# VI_595X5_V1_1.net
KiCad netlist of a schematic drawn in Altium Designer
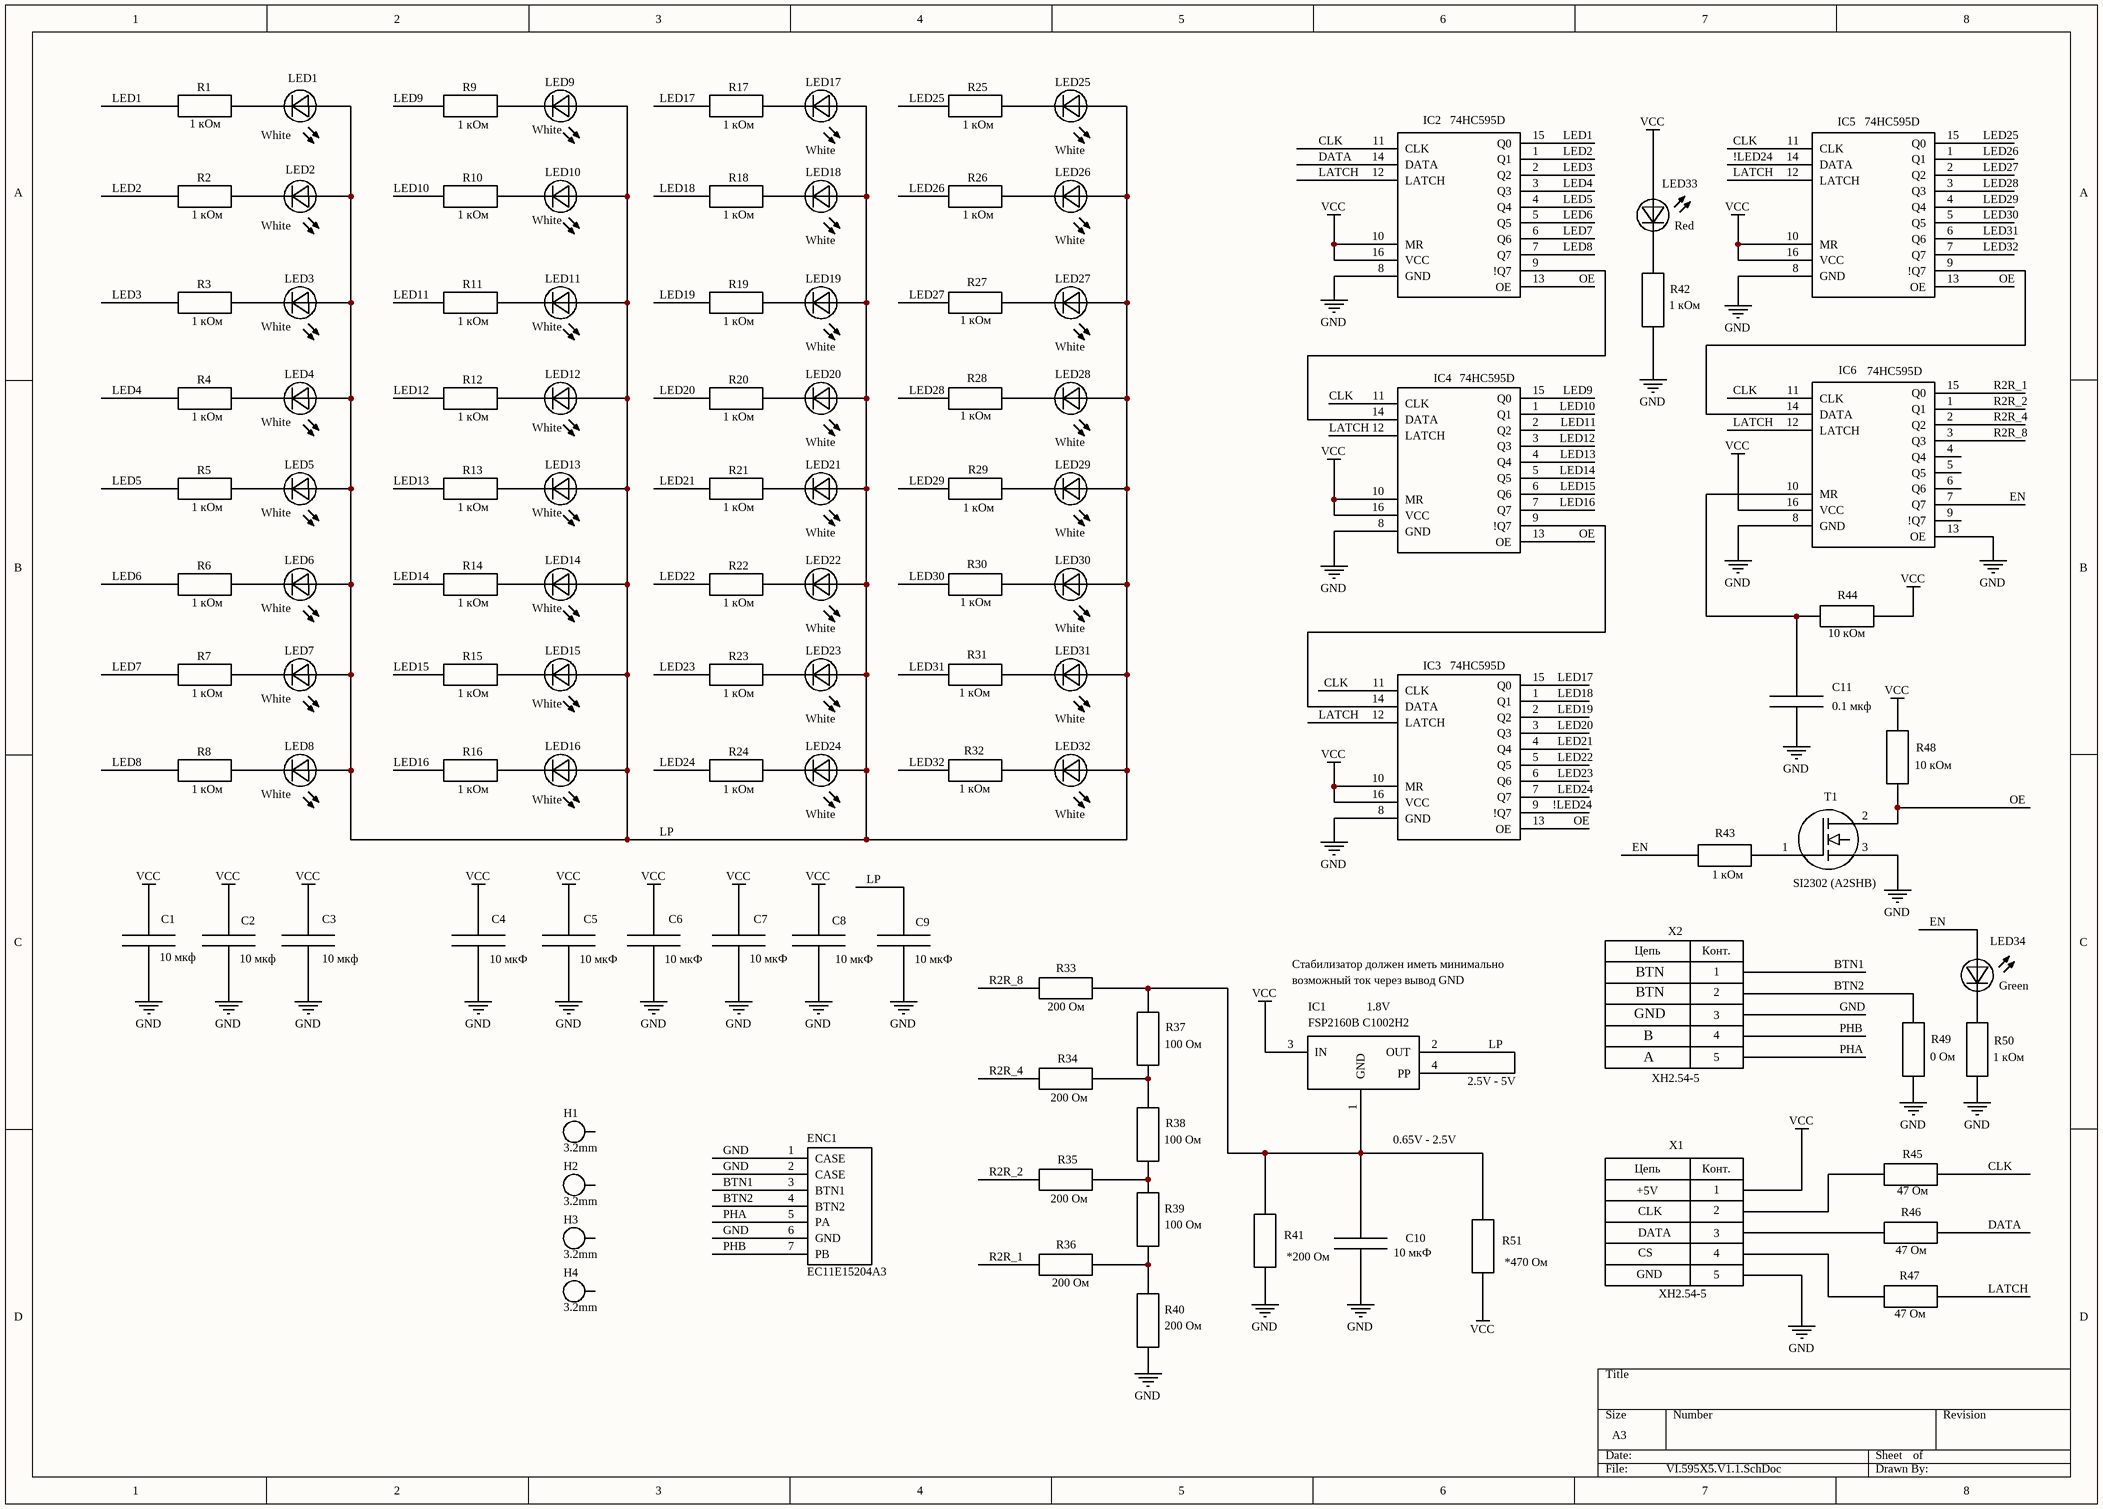
[diagram p0: VI.595X5.V1.1.SchDoc]

(export (version "E")
  (design (tool "Eeschema 10.0.6"))
  (components
    (comp (ref "C1")
      (value "10 мкф")
      (footprint "Конденсатор SMD Case 1206")
      (libsource (lib "S83") (part "Конденсатор"))
    )
    (comp (ref "C2")
      (value "10 мкф")
      (footprint "Конденсатор SMD Case 1206")
      (libsource (lib "S83") (part "Конденсатор"))
    )
    (comp (ref "C3")
      (value "10 мкф")
      (footprint "Конденсатор SMD Case 1206")
      (libsource (lib "S83") (part "Конденсатор"))
    )
    (comp (ref "C4")
      (value "10 мкФ")
      (footprint "Конденсатор SMD Case 1206")
      (libsource (lib "S83") (part "Конденсатор"))
    )
    (comp (ref "C5")
      (value "10 мкФ")
      (footprint "Конденсатор SMD Case 1206")
      (libsource (lib "S83") (part "Конденсатор"))
    )
    (comp (ref "C6")
      (value "10 мкФ")
      (footprint "Конденсатор SMD Case 1206")
      (libsource (lib "S83") (part "Конденсатор"))
    )
    (comp (ref "C7")
      (value "10 мкФ")
      (footprint "Конденсатор SMD Case 1206")
      (libsource (lib "S83") (part "Конденсатор"))
    )
    (comp (ref "C8")
      (value "10 мкФ")
      (footprint "Конденсатор SMD Case 1206")
      (libsource (lib "S83") (part "Конденсатор"))
    )
    (comp (ref "C9")
      (value "10 мкФ")
      (footprint "Конденсатор SMD Case 1206")
      (libsource (lib "S83") (part "Конденсатор"))
    )
    (comp (ref "C10")
      (value "10 мкФ")
      (footprint "Конденсатор SMD Case 1206")
      (libsource (lib "S83") (part "Конденсатор"))
    )
    (comp (ref "C11")
      (value "0.1 мкф")
      (footprint "Конденсатор SMD Case 1206")
      (libsource (lib "S83") (part "Конденсатор"))
    )
    (comp (ref "ENC1")
      (value "EC11E15204A3")
      (footprint "Encoder")
      (libsource (lib "S83") (part "Encoder_01"))
    )
    (comp (ref "H1")
      (value "3.2mm")
      (footprint "Отверстие 3,2")
      (libsource (lib "S83") (part "Отверстие монтажное"))
    )
    (comp (ref "H2")
      (value "3.2mm")
      (footprint "Отверстие 3,2")
      (libsource (lib "S83") (part "Отверстие монтажное"))
    )
    (comp (ref "H3")
      (value "3.2mm")
      (footprint "Отверстие 3,2")
      (libsource (lib "S83") (part "Отверстие монтажное"))
    )
    (comp (ref "H4")
      (value "3.2mm")
      (footprint "Отверстие 3,2")
      (libsource (lib "S83") (part "Отверстие монтажное"))
    )
    (comp (ref "IC1")
      (value "FSP2160B C1002H2")
      (footprint "SOT-223")
      (libsource (lib "S83_IC") (part "FSP2160B J1003H1"))
    )
    (comp (ref "IC2") (value "74HC595D") (footprint "SO-16") (libsource (lib "S83_IC") (part "74HC595D")))
    (comp (ref "IC3") (value "74HC595D") (footprint "SO-16") (libsource (lib "S83_IC") (part "74HC595D")))
    (comp (ref "IC4") (value "74HC595D") (footprint "SO-16") (libsource (lib "S83_IC") (part "74HC595D")))
    (comp (ref "IC5") (value "74HC595D") (footprint "SO-16") (libsource (lib "S83_IC") (part "74HC595D")))
    (comp (ref "IC6") (value "74HC595D") (footprint "SO-16") (libsource (lib "S83_IC") (part "74HC595D")))
    (comp (ref "LED1")
      (value "White")
      (footprint "Светодиод  5x2 mm")
      (libsource (lib "S83") (part "Светодиод"))
    )
    (comp (ref "LED2")
      (value "White")
      (footprint "Светодиод  5x2 mm")
      (libsource (lib "S83") (part "Светодиод"))
    )
    (comp (ref "LED3")
      (value "White")
      (footprint "Светодиод  5x2 mm")
      (libsource (lib "S83") (part "Светодиод"))
    )
    (comp (ref "LED4")
      (value "White")
      (footprint "Светодиод  5x2 mm")
      (libsource (lib "S83") (part "Светодиод"))
    )
    (comp (ref "LED5")
      (value "White")
      (footprint "Светодиод  5x2 mm")
      (libsource (lib "S83") (part "Светодиод"))
    )
    (comp (ref "LED6")
      (value "White")
      (footprint "Светодиод  5x2 mm")
      (libsource (lib "S83") (part "Светодиод"))
    )
    (comp (ref "LED7")
      (value "White")
      (footprint "Светодиод  5x2 mm")
      (libsource (lib "S83") (part "Светодиод"))
    )
    (comp (ref "LED8")
      (value "White")
      (footprint "Светодиод  5x2 mm")
      (libsource (lib "S83") (part "Светодиод"))
    )
    (comp (ref "LED9")
      (value "White")
      (footprint "Светодиод  5x2 mm")
      (libsource (lib "S83") (part "Светодиод"))
    )
    (comp (ref "LED10")
      (value "White")
      (footprint "Светодиод  5x2 mm")
      (libsource (lib "S83") (part "Светодиод"))
    )
    (comp (ref "LED11")
      (value "White")
      (footprint "Светодиод  5x2 mm")
      (libsource (lib "S83") (part "Светодиод"))
    )
    (comp (ref "LED12")
      (value "White")
      (footprint "Светодиод  5x2 mm")
      (libsource (lib "S83") (part "Светодиод"))
    )
    (comp (ref "LED13")
      (value "White")
      (footprint "Светодиод  5x2 mm")
      (libsource (lib "S83") (part "Светодиод"))
    )
    (comp (ref "LED14")
      (value "White")
      (footprint "Светодиод  5x2 mm")
      (libsource (lib "S83") (part "Светодиод"))
    )
    (comp (ref "LED15")
      (value "White")
      (footprint "Светодиод  5x2 mm")
      (libsource (lib "S83") (part "Светодиод"))
    )
    (comp (ref "LED16")
      (value "White")
      (footprint "Светодиод  5x2 mm")
      (libsource (lib "S83") (part "Светодиод"))
    )
    (comp (ref "LED17")
      (value "White")
      (footprint "Светодиод  5x2 mm")
      (libsource (lib "S83") (part "Светодиод"))
    )
    (comp (ref "LED18")
      (value "White")
      (footprint "Светодиод  5x2 mm")
      (libsource (lib "S83") (part "Светодиод"))
    )
    (comp (ref "LED19")
      (value "White")
      (footprint "Светодиод  5x2 mm")
      (libsource (lib "S83") (part "Светодиод"))
    )
    (comp (ref "LED20")
      (value "White")
      (footprint "Светодиод  5x2 mm")
      (libsource (lib "S83") (part "Светодиод"))
    )
    (comp (ref "LED21")
      (value "White")
      (footprint "Светодиод  5x2 mm")
      (libsource (lib "S83") (part "Светодиод"))
    )
    (comp (ref "LED22")
      (value "White")
      (footprint "Светодиод  5x2 mm")
      (libsource (lib "S83") (part "Светодиод"))
    )
    (comp (ref "LED23")
      (value "White")
      (footprint "Светодиод  5x2 mm")
      (libsource (lib "S83") (part "Светодиод"))
    )
    (comp (ref "LED24")
      (value "White")
      (footprint "Светодиод  5x2 mm")
      (libsource (lib "S83") (part "Светодиод"))
    )
    (comp (ref "LED25")
      (value "White")
      (footprint "Светодиод  5x2 mm")
      (libsource (lib "S83") (part "Светодиод"))
    )
    (comp (ref "LED26")
      (value "White")
      (footprint "Светодиод  5x2 mm")
      (libsource (lib "S83") (part "Светодиод"))
    )
    (comp (ref "LED27")
      (value "White")
      (footprint "Светодиод  5x2 mm")
      (libsource (lib "S83") (part "Светодиод"))
    )
    (comp (ref "LED28")
      (value "White")
      (footprint "Светодиод  5x2 mm")
      (libsource (lib "S83") (part "Светодиод"))
    )
    (comp (ref "LED29")
      (value "White")
      (footprint "Светодиод  5x2 mm")
      (libsource (lib "S83") (part "Светодиод"))
    )
    (comp (ref "LED30")
      (value "White")
      (footprint "Светодиод  5x2 mm")
      (libsource (lib "S83") (part "Светодиод"))
    )
    (comp (ref "LED31")
      (value "White")
      (footprint "Светодиод  5x2 mm")
      (libsource (lib "S83") (part "Светодиод"))
    )
    (comp (ref "LED32")
      (value "White")
      (footprint "Светодиод  5x2 mm")
      (libsource (lib "S83") (part "Светодиод"))
    )
    (comp (ref "LED33")
      (value "Red")
      (footprint "SMD 1206 Светодиод ВАЙТ")
      (libsource (lib "S83") (part "Светодиод"))
    )
    (comp (ref "LED34")
      (value "Green")
      (footprint "SMD 1206 Светодиод ВАЙТ")
      (libsource (lib "S83") (part "Светодиод"))
    )
    (comp (ref "R1")
      (value "1 кОм")
      (footprint "SMD 0805 Резистор")
      (libsource (lib "S83") (part "Резистор"))
    )
    (comp (ref "R2")
      (value "1 кОм")
      (footprint "SMD 0805 Резистор")
      (libsource (lib "S83") (part "Резистор"))
    )
    (comp (ref "R3")
      (value "1 кОм")
      (footprint "SMD 0805 Резистор")
      (libsource (lib "S83") (part "Резистор"))
    )
    (comp (ref "R4")
      (value "1 кОм")
      (footprint "SMD 0805 Резистор")
      (libsource (lib "S83") (part "Резистор"))
    )
    (comp (ref "R5")
      (value "1 кОм")
      (footprint "SMD 0805 Резистор")
      (libsource (lib "S83") (part "Резистор"))
    )
    (comp (ref "R6")
      (value "1 кОм")
      (footprint "SMD 0805 Резистор")
      (libsource (lib "S83") (part "Резистор"))
    )
    (comp (ref "R7")
      (value "1 кОм")
      (footprint "SMD 0805 Резистор")
      (libsource (lib "S83") (part "Резистор"))
    )
    (comp (ref "R8")
      (value "1 кОм")
      (footprint "SMD 0805 Резистор")
      (libsource (lib "S83") (part "Резистор"))
    )
    (comp (ref "R9")
      (value "1 кОм")
      (footprint "SMD 0805 Резистор")
      (libsource (lib "S83") (part "Резистор"))
    )
    (comp (ref "R10")
      (value "1 кОм")
      (footprint "SMD 0805 Резистор")
      (libsource (lib "S83") (part "Резистор"))
    )
    (comp (ref "R11")
      (value "1 кОм")
      (footprint "SMD 0805 Резистор")
      (libsource (lib "S83") (part "Резистор"))
    )
    (comp (ref "R12")
      (value "1 кОм")
      (footprint "SMD 0805 Резистор")
      (libsource (lib "S83") (part "Резистор"))
    )
    (comp (ref "R13")
      (value "1 кОм")
      (footprint "SMD 0805 Резистор")
      (libsource (lib "S83") (part "Резистор"))
    )
    (comp (ref "R14")
      (value "1 кОм")
      (footprint "SMD 0805 Резистор")
      (libsource (lib "S83") (part "Резистор"))
    )
    (comp (ref "R15")
      (value "1 кОм")
      (footprint "SMD 0805 Резистор")
      (libsource (lib "S83") (part "Резистор"))
    )
    (comp (ref "R16")
      (value "1 кОм")
      (footprint "SMD 0805 Резистор")
      (libsource (lib "S83") (part "Резистор"))
    )
    (comp (ref "R17")
      (value "1 кОм")
      (footprint "SMD 0805 Резистор")
      (libsource (lib "S83") (part "Резистор"))
    )
    (comp (ref "R18")
      (value "1 кОм")
      (footprint "SMD 0805 Резистор")
      (libsource (lib "S83") (part "Резистор"))
    )
    (comp (ref "R19")
      (value "1 кОм")
      (footprint "SMD 0805 Резистор")
      (libsource (lib "S83") (part "Резистор"))
    )
    (comp (ref "R20")
      (value "1 кОм")
      (footprint "SMD 0805 Резистор")
      (libsource (lib "S83") (part "Резистор"))
    )
    (comp (ref "R21")
      (value "1 кОм")
      (footprint "SMD 0805 Резистор")
      (libsource (lib "S83") (part "Резистор"))
    )
    (comp (ref "R22")
      (value "1 кОм")
      (footprint "SMD 0805 Резистор")
      (libsource (lib "S83") (part "Резистор"))
    )
    (comp (ref "R23")
      (value "1 кОм")
      (footprint "SMD 0805 Резистор")
      (libsource (lib "S83") (part "Резистор"))
    )
    (comp (ref "R24")
      (value "1 кОм")
      (footprint "SMD 0805 Резистор")
      (libsource (lib "S83") (part "Резистор"))
    )
    (comp (ref "R25")
      (value "1 кОм")
      (footprint "SMD 0805 Резистор")
      (libsource (lib "S83") (part "Резистор"))
    )
    (comp (ref "R26")
      (value "1 кОм")
      (footprint "SMD 0805 Резистор")
      (libsource (lib "S83") (part "Резистор"))
    )
    (comp (ref "R27")
      (value "1 кОм")
      (footprint "SMD 0805 Резистор")
      (libsource (lib "S83") (part "Резистор"))
    )
    (comp (ref "R28")
      (value "1 кОм")
      (footprint "SMD 0805 Резистор")
      (libsource (lib "S83") (part "Резистор"))
    )
    (comp (ref "R29")
      (value "1 кОм")
      (footprint "SMD 0805 Резистор")
      (libsource (lib "S83") (part "Резистор"))
    )
    (comp (ref "R30")
      (value "1 кОм")
      (footprint "SMD 0805 Резистор")
      (libsource (lib "S83") (part "Резистор"))
    )
    (comp (ref "R31")
      (value "1 кОм")
      (footprint "SMD 0805 Резистор")
      (libsource (lib "S83") (part "Резистор"))
    )
    (comp (ref "R32")
      (value "1 кОм")
      (footprint "SMD 0805 Резистор")
      (libsource (lib "S83") (part "Резистор"))
    )
    (comp (ref "R33")
      (value "200 Ом")
      (footprint "SMD 0805 Резистор")
      (libsource (lib "S83") (part "Резистор"))
    )
    (comp (ref "R34")
      (value "200 Ом")
      (footprint "SMD 0805 Резистор")
      (libsource (lib "S83") (part "Резистор"))
    )
    (comp (ref "R35")
      (value "200 Ом")
      (footprint "SMD 0805 Резистор")
      (libsource (lib "S83") (part "Резистор"))
    )
    (comp (ref "R36")
      (value "200 Ом")
      (footprint "SMD 0805 Резистор")
      (libsource (lib "S83") (part "Резистор"))
    )
    (comp (ref "R37")
      (value "100 Ом")
      (footprint "SMD 0805 Резистор")
      (libsource (lib "S83") (part "Резистор"))
    )
    (comp (ref "R38")
      (value "100 Ом")
      (footprint "SMD 0805 Резистор")
      (libsource (lib "S83") (part "Резистор"))
    )
    (comp (ref "R39")
      (value "100 Ом")
      (footprint "SMD 0805 Резистор")
      (libsource (lib "S83") (part "Резистор"))
    )
    (comp (ref "R40")
      (value "200 Ом")
      (footprint "SMD 0805 Резистор")
      (libsource (lib "S83") (part "Резистор"))
    )
    (comp (ref "R41")
      (value "*200 Ом")
      (footprint "SMD 0805 Резистор")
      (libsource (lib "S83") (part "Резистор"))
    )
    (comp (ref "R42")
      (value "1 кОм")
      (footprint "SMD 0805 Резистор")
      (libsource (lib "S83") (part "Резистор"))
    )
    (comp (ref "R43")
      (value "1 кОм")
      (footprint "SMD 0805 Резистор")
      (libsource (lib "S83") (part "Резистор"))
    )
    (comp (ref "R44")
      (value "10 кОм")
      (footprint "SMD 0805 Резистор")
      (libsource (lib "S83") (part "Резистор"))
    )
    (comp (ref "R45")
      (value "47 Ом")
      (footprint "SMD 0805 Резистор")
      (libsource (lib "S83") (part "Резистор"))
    )
    (comp (ref "R46")
      (value "47 Ом")
      (footprint "SMD 0805 Резистор")
      (libsource (lib "S83") (part "Резистор"))
    )
    (comp (ref "R47")
      (value "47 Ом")
      (footprint "SMD 0805 Резистор")
      (libsource (lib "S83") (part "Резистор"))
    )
    (comp (ref "R48")
      (value "10 кОм")
      (footprint "SMD 0805 Резистор")
      (libsource (lib "S83") (part "Резистор"))
    )
    (comp (ref "R49")
      (value "0 Ом")
      (footprint "SMD 0805 Резистор")
      (libsource (lib "S83") (part "Резистор"))
    )
    (comp (ref "R50")
      (value "1 кОм")
      (footprint "SMD 0805 Резистор")
      (libsource (lib "S83") (part "Резистор"))
    )
    (comp (ref "R51")
      (value "*470 Ом")
      (footprint "SMD 0805 Резистор")
      (libsource (lib "S83") (part "Резистор"))
    )
    (comp (ref "T1")
      (value "SI2302 (A2SHB)")
      (footprint "SMD SOT-23 Транзистор 3 pin")
      (libsource (lib "S83") (part "Транзистор MOSFET N-конал (как n-p-n)"))
    )
    (comp (ref "X1")
      (value "XH2.54-5")
      (footprint "(1x5)pin XH 2.54 Header")
      (libsource (lib "S83_connectors") (part "(1x5) pin 2.54 Header"))
    )
    (comp (ref "X2")
      (value "XH2.54-5")
      (footprint "(1x5)pin XH 2.54 Header")
      (libsource (lib "S83_connectors") (part "(1x5) pin 2.54 Header"))
    )
  )
  (nets
    (net (code "1") (name "/!LED24") (class "Default")
      (node (ref "IC3") (pin "9") (pinfunction "!Q7_9") (pintype "passive"))
      (node (ref "IC5") (pin "14") (pinfunction "DATA_14") (pintype "passive"))
    )
    (net (code "2") (name "/BTN1") (class "Default")
      (node (ref "ENC1") (pin "3") (pinfunction "BTN1_3") (pintype "passive"))
      (node (ref "X2") (pin "1") (pinfunction "1_1") (pintype "passive"))
    )
    (net (code "3") (name "/BTN2") (class "Default")
      (node (ref "ENC1") (pin "4") (pinfunction "BTN2_4") (pintype "passive"))
      (node (ref "R49") (pin "2") (pinfunction "right_2") (pintype "passive"))
      (node (ref "X2") (pin "2") (pinfunction "2_2") (pintype "passive"))
    )
    (net (code "4") (name "/CLK") (class "Default")
      (node (ref "IC2") (pin "11") (pinfunction "CLK_11") (pintype "passive"))
      (node (ref "IC3") (pin "11") (pinfunction "CLK_11") (pintype "passive"))
      (node (ref "IC4") (pin "11") (pinfunction "CLK_11") (pintype "passive"))
      (node (ref "IC5") (pin "11") (pinfunction "CLK_11") (pintype "passive"))
      (node (ref "IC6") (pin "11") (pinfunction "CLK_11") (pintype "passive"))
      (node (ref "R45") (pin "1") (pinfunction "left_1") (pintype "passive"))
    )
    (net (code "5") (name "/DATA") (class "Default")
      (node (ref "IC2") (pin "14") (pinfunction "DATA_14") (pintype "passive"))
      (node (ref "R46") (pin "1") (pinfunction "left_1") (pintype "passive"))
    )
    (net (code "6") (name "/EN") (class "Default")
      (node (ref "IC6") (pin "7") (pinfunction "Q7_7") (pintype "passive"))
      (node (ref "LED34") (pin "1") (pinfunction "А_1") (pintype "passive"))
      (node (ref "R43") (pin "2") (pinfunction "right_2") (pintype "passive"))
    )
    (net (code "7") (name "/LATCH") (class "Default")
      (node (ref "IC2") (pin "12") (pinfunction "LATCH_12") (pintype "passive"))
      (node (ref "IC3") (pin "12") (pinfunction "LATCH_12") (pintype "passive"))
      (node (ref "IC4") (pin "12") (pinfunction "LATCH_12") (pintype "passive"))
      (node (ref "IC5") (pin "12") (pinfunction "LATCH_12") (pintype "passive"))
      (node (ref "IC6") (pin "12") (pinfunction "LATCH_12") (pintype "passive"))
      (node (ref "R47") (pin "1") (pinfunction "left_1") (pintype "passive"))
    )
    (net (code "8") (name "/LED1") (class "Default")
      (node (ref "IC2") (pin "15") (pinfunction "Q0_15") (pintype "passive"))
      (node (ref "R1") (pin "1") (pinfunction "left_1") (pintype "passive"))
    )
    (net (code "9") (name "/LED2") (class "Default")
      (node (ref "IC2") (pin "1") (pinfunction "Q1_1") (pintype "passive"))
      (node (ref "R2") (pin "1") (pinfunction "left_1") (pintype "passive"))
    )
    (net (code "10") (name "/LED3") (class "Default")
      (node (ref "IC2") (pin "2") (pinfunction "Q2_2") (pintype "passive"))
      (node (ref "R3") (pin "1") (pinfunction "left_1") (pintype "passive"))
    )
    (net (code "11") (name "/LED4") (class "Default")
      (node (ref "IC2") (pin "3") (pinfunction "Q3_3") (pintype "passive"))
      (node (ref "R4") (pin "1") (pinfunction "left_1") (pintype "passive"))
    )
    (net (code "12") (name "/LED5") (class "Default")
      (node (ref "IC2") (pin "4") (pinfunction "Q4_4") (pintype "passive"))
      (node (ref "R5") (pin "1") (pinfunction "left_1") (pintype "passive"))
    )
    (net (code "13") (name "/LED6") (class "Default")
      (node (ref "IC2") (pin "5") (pinfunction "Q5_5") (pintype "passive"))
      (node (ref "R6") (pin "1") (pinfunction "left_1") (pintype "passive"))
    )
    (net (code "14") (name "/LED7") (class "Default")
      (node (ref "IC2") (pin "6") (pinfunction "Q6_6") (pintype "passive"))
      (node (ref "R7") (pin "1") (pinfunction "left_1") (pintype "passive"))
    )
    (net (code "15") (name "/LED8") (class "Default")
      (node (ref "IC2") (pin "7") (pinfunction "Q7_7") (pintype "passive"))
      (node (ref "R8") (pin "1") (pinfunction "left_1") (pintype "passive"))
    )
    (net (code "16") (name "/LED9") (class "Default")
      (node (ref "IC4") (pin "15") (pinfunction "Q0_15") (pintype "passive"))
      (node (ref "R9") (pin "1") (pinfunction "left_1") (pintype "passive"))
    )
    (net (code "17") (name "/LED10") (class "Default")
      (node (ref "IC4") (pin "1") (pinfunction "Q1_1") (pintype "passive"))
      (node (ref "R10") (pin "1") (pinfunction "left_1") (pintype "passive"))
    )
    (net (code "18") (name "/LED11") (class "Default")
      (node (ref "IC4") (pin "2") (pinfunction "Q2_2") (pintype "passive"))
      (node (ref "R11") (pin "1") (pinfunction "left_1") (pintype "passive"))
    )
    (net (code "19") (name "/LED12") (class "Default")
      (node (ref "IC4") (pin "3") (pinfunction "Q3_3") (pintype "passive"))
      (node (ref "R12") (pin "1") (pinfunction "left_1") (pintype "passive"))
    )
    (net (code "20") (name "/LED13") (class "Default")
      (node (ref "IC4") (pin "4") (pinfunction "Q4_4") (pintype "passive"))
      (node (ref "R13") (pin "1") (pinfunction "left_1") (pintype "passive"))
    )
    (net (code "21") (name "/LED14") (class "Default")
      (node (ref "IC4") (pin "5") (pinfunction "Q5_5") (pintype "passive"))
      (node (ref "R14") (pin "1") (pinfunction "left_1") (pintype "passive"))
    )
    (net (code "22") (name "/LED15") (class "Default")
      (node (ref "IC4") (pin "6") (pinfunction "Q6_6") (pintype "passive"))
      (node (ref "R15") (pin "1") (pinfunction "left_1") (pintype "passive"))
    )
    (net (code "23") (name "/LED16") (class "Default")
      (node (ref "IC4") (pin "7") (pinfunction "Q7_7") (pintype "passive"))
      (node (ref "R16") (pin "1") (pinfunction "left_1") (pintype "passive"))
    )
    (net (code "24") (name "/LED17") (class "Default")
      (node (ref "IC3") (pin "15") (pinfunction "Q0_15") (pintype "passive"))
      (node (ref "R17") (pin "1") (pinfunction "left_1") (pintype "passive"))
    )
    (net (code "25") (name "/LED18") (class "Default")
      (node (ref "IC3") (pin "1") (pinfunction "Q1_1") (pintype "passive"))
      (node (ref "R18") (pin "1") (pinfunction "left_1") (pintype "passive"))
    )
    (net (code "26") (name "/LED19") (class "Default")
      (node (ref "IC3") (pin "2") (pinfunction "Q2_2") (pintype "passive"))
      (node (ref "R19") (pin "1") (pinfunction "left_1") (pintype "passive"))
    )
    (net (code "27") (name "/LED20") (class "Default")
      (node (ref "IC3") (pin "3") (pinfunction "Q3_3") (pintype "passive"))
      (node (ref "R20") (pin "1") (pinfunction "left_1") (pintype "passive"))
    )
    (net (code "28") (name "/LED21") (class "Default")
      (node (ref "IC3") (pin "4") (pinfunction "Q4_4") (pintype "passive"))
      (node (ref "R21") (pin "1") (pinfunction "left_1") (pintype "passive"))
    )
    (net (code "29") (name "/LED22") (class "Default")
      (node (ref "IC3") (pin "5") (pinfunction "Q5_5") (pintype "passive"))
      (node (ref "R22") (pin "1") (pinfunction "left_1") (pintype "passive"))
    )
    (net (code "30") (name "/LED23") (class "Default")
      (node (ref "IC3") (pin "6") (pinfunction "Q6_6") (pintype "passive"))
      (node (ref "R23") (pin "1") (pinfunction "left_1") (pintype "passive"))
    )
    (net (code "31") (name "/LED24") (class "Default")
      (node (ref "IC3") (pin "7") (pinfunction "Q7_7") (pintype "passive"))
      (node (ref "R24") (pin "1") (pinfunction "left_1") (pintype "passive"))
    )
    (net (code "32") (name "/LED25") (class "Default")
      (node (ref "IC5") (pin "15") (pinfunction "Q0_15") (pintype "passive"))
      (node (ref "R25") (pin "1") (pinfunction "left_1") (pintype "passive"))
    )
    (net (code "33") (name "/LED26") (class "Default")
      (node (ref "IC5") (pin "1") (pinfunction "Q1_1") (pintype "passive"))
      (node (ref "R26") (pin "1") (pinfunction "left_1") (pintype "passive"))
    )
    (net (code "34") (name "/LED27") (class "Default")
      (node (ref "IC5") (pin "2") (pinfunction "Q2_2") (pintype "passive"))
      (node (ref "R27") (pin "1") (pinfunction "left_1") (pintype "passive"))
    )
    (net (code "35") (name "/LED28") (class "Default")
      (node (ref "IC5") (pin "3") (pinfunction "Q3_3") (pintype "passive"))
      (node (ref "R28") (pin "1") (pinfunction "left_1") (pintype "passive"))
    )
    (net (code "36") (name "/LED29") (class "Default")
      (node (ref "IC5") (pin "4") (pinfunction "Q4_4") (pintype "passive"))
      (node (ref "R29") (pin "1") (pinfunction "left_1") (pintype "passive"))
    )
    (net (code "37") (name "/LED30") (class "Default")
      (node (ref "IC5") (pin "5") (pinfunction "Q5_5") (pintype "passive"))
      (node (ref "R30") (pin "1") (pinfunction "left_1") (pintype "passive"))
    )
    (net (code "38") (name "/LED31") (class "Default")
      (node (ref "IC5") (pin "6") (pinfunction "Q6_6") (pintype "passive"))
      (node (ref "R31") (pin "1") (pinfunction "left_1") (pintype "passive"))
    )
    (net (code "39") (name "/LED32") (class "Default")
      (node (ref "IC5") (pin "7") (pinfunction "Q7_7") (pintype "passive"))
      (node (ref "R32") (pin "1") (pinfunction "left_1") (pintype "passive"))
    )
    (net (code "40") (name "/LP") (class "Default")
      (node (ref "C9") (pin "1") (pinfunction "+_1") (pintype "passive"))
      (node (ref "IC1") (pin "2") (pinfunction "OUT_2") (pintype "passive"))
      (node (ref "IC1") (pin "4") (pinfunction "PP_4") (pintype "passive"))
      (node (ref "LED1") (pin "1") (pinfunction "А_1") (pintype "passive"))
      (node (ref "LED10") (pin "1") (pinfunction "А_1") (pintype "passive"))
      (node (ref "LED11") (pin "1") (pinfunction "А_1") (pintype "passive"))
      (node (ref "LED12") (pin "1") (pinfunction "А_1") (pintype "passive"))
      (node (ref "LED13") (pin "1") (pinfunction "А_1") (pintype "passive"))
      (node (ref "LED14") (pin "1") (pinfunction "А_1") (pintype "passive"))
      (node (ref "LED15") (pin "1") (pinfunction "А_1") (pintype "passive"))
      (node (ref "LED16") (pin "1") (pinfunction "А_1") (pintype "passive"))
      (node (ref "LED17") (pin "1") (pinfunction "А_1") (pintype "passive"))
      (node (ref "LED18") (pin "1") (pinfunction "А_1") (pintype "passive"))
      (node (ref "LED19") (pin "1") (pinfunction "А_1") (pintype "passive"))
      (node (ref "LED2") (pin "1") (pinfunction "А_1") (pintype "passive"))
      (node (ref "LED20") (pin "1") (pinfunction "А_1") (pintype "passive"))
      (node (ref "LED21") (pin "1") (pinfunction "А_1") (pintype "passive"))
      (node (ref "LED22") (pin "1") (pinfunction "А_1") (pintype "passive"))
      (node (ref "LED23") (pin "1") (pinfunction "А_1") (pintype "passive"))
      (node (ref "LED24") (pin "1") (pinfunction "А_1") (pintype "passive"))
      (node (ref "LED25") (pin "1") (pinfunction "А_1") (pintype "passive"))
      (node (ref "LED26") (pin "1") (pinfunction "А_1") (pintype "passive"))
      (node (ref "LED27") (pin "1") (pinfunction "А_1") (pintype "passive"))
      (node (ref "LED28") (pin "1") (pinfunction "А_1") (pintype "passive"))
      (node (ref "LED29") (pin "1") (pinfunction "А_1") (pintype "passive"))
      (node (ref "LED3") (pin "1") (pinfunction "А_1") (pintype "passive"))
      (node (ref "LED30") (pin "1") (pinfunction "А_1") (pintype "passive"))
      (node (ref "LED31") (pin "1") (pinfunction "А_1") (pintype "passive"))
      (node (ref "LED32") (pin "1") (pinfunction "А_1") (pintype "passive"))
      (node (ref "LED4") (pin "1") (pinfunction "А_1") (pintype "passive"))
      (node (ref "LED5") (pin "1") (pinfunction "А_1") (pintype "passive"))
      (node (ref "LED6") (pin "1") (pinfunction "А_1") (pintype "passive"))
      (node (ref "LED7") (pin "1") (pinfunction "А_1") (pintype "passive"))
      (node (ref "LED8") (pin "1") (pinfunction "А_1") (pintype "passive"))
      (node (ref "LED9") (pin "1") (pinfunction "А_1") (pintype "passive"))
    )
    (net (code "41") (name "/OE") (class "Default")
      (node (ref "IC2") (pin "13") (pinfunction "OE_13") (pintype "passive"))
      (node (ref "IC3") (pin "13") (pinfunction "OE_13") (pintype "passive"))
      (node (ref "IC4") (pin "13") (pinfunction "OE_13") (pintype "passive"))
      (node (ref "IC5") (pin "13") (pinfunction "OE_13") (pintype "passive"))
      (node (ref "R48") (pin "2") (pinfunction "right_2") (pintype "passive"))
      (node (ref "T1") (pin "2") (pinfunction "2_2") (pintype "passive"))
    )
    (net (code "42") (name "/PHA") (class "Default")
      (node (ref "ENC1") (pin "5") (pinfunction "PA_5") (pintype "passive"))
      (node (ref "X2") (pin "5") (pinfunction "5_5") (pintype "passive"))
    )
    (net (code "43") (name "/PHB") (class "Default")
      (node (ref "ENC1") (pin "7") (pinfunction "PB_7") (pintype "passive"))
      (node (ref "X2") (pin "4") (pinfunction "4_4") (pintype "passive"))
    )
    (net (code "44") (name "/R2R_1") (class "Default")
      (node (ref "IC6") (pin "15") (pinfunction "Q0_15") (pintype "passive"))
      (node (ref "R36") (pin "1") (pinfunction "left_1") (pintype "passive"))
    )
    (net (code "45") (name "/R2R_2") (class "Default")
      (node (ref "IC6") (pin "1") (pinfunction "Q1_1") (pintype "passive"))
      (node (ref "R35") (pin "1") (pinfunction "left_1") (pintype "passive"))
    )
    (net (code "46") (name "/R2R_4") (class "Default")
      (node (ref "IC6") (pin "2") (pinfunction "Q2_2") (pintype "passive"))
      (node (ref "R34") (pin "1") (pinfunction "left_1") (pintype "passive"))
    )
    (net (code "47") (name "/R2R_8") (class "Default")
      (node (ref "IC6") (pin "3") (pinfunction "Q3_3") (pintype "passive"))
      (node (ref "R33") (pin "1") (pinfunction "left_1") (pintype "passive"))
    )
    (net (code "48") (name "GND") (class "Default")
      (node (ref "C1") (pin "2") (pinfunction "-_2") (pintype "passive"))
      (node (ref "C10") (pin "2") (pinfunction "-_2") (pintype "passive"))
      (node (ref "C11") (pin "2") (pinfunction "-_2") (pintype "passive"))
      (node (ref "C2") (pin "2") (pinfunction "-_2") (pintype "passive"))
      (node (ref "C3") (pin "2") (pinfunction "-_2") (pintype "passive"))
      (node (ref "C4") (pin "2") (pinfunction "-_2") (pintype "passive"))
      (node (ref "C5") (pin "2") (pinfunction "-_2") (pintype "passive"))
      (node (ref "C6") (pin "2") (pinfunction "-_2") (pintype "passive"))
      (node (ref "C7") (pin "2") (pinfunction "-_2") (pintype "passive"))
      (node (ref "C8") (pin "2") (pinfunction "-_2") (pintype "passive"))
      (node (ref "C9") (pin "2") (pinfunction "-_2") (pintype "passive"))
      (node (ref "ENC1") (pin "1") (pinfunction "CASE_1") (pintype "passive"))
      (node (ref "ENC1") (pin "2") (pinfunction "CASE_2") (pintype "passive"))
      (node (ref "ENC1") (pin "6") (pinfunction "GND_6") (pintype "passive"))
      (node (ref "IC2") (pin "8") (pinfunction "GND_8") (pintype "passive"))
      (node (ref "IC3") (pin "8") (pinfunction "GND_8") (pintype "passive"))
      (node (ref "IC4") (pin "8") (pinfunction "GND_8") (pintype "passive"))
      (node (ref "IC5") (pin "8") (pinfunction "GND_8") (pintype "passive"))
      (node (ref "IC6") (pin "13") (pinfunction "OE_13") (pintype "passive"))
      (node (ref "IC6") (pin "8") (pinfunction "GND_8") (pintype "passive"))
      (node (ref "R40") (pin "1") (pinfunction "left_1") (pintype "passive"))
      (node (ref "R41") (pin "1") (pinfunction "left_1") (pintype "passive"))
      (node (ref "R42") (pin "1") (pinfunction "left_1") (pintype "passive"))
      (node (ref "R49") (pin "1") (pinfunction "left_1") (pintype "passive"))
      (node (ref "R50") (pin "1") (pinfunction "left_1") (pintype "passive"))
      (node (ref "T1") (pin "3") (pinfunction "3_3") (pintype "passive"))
      (node (ref "X1") (pin "5") (pinfunction "5_5") (pintype "passive"))
      (node (ref "X2") (pin "3") (pinfunction "3_3") (pintype "passive"))
    )
    (net (code "49") (name "Net-(C10-+)") (class "Default")
      (node (ref "C10") (pin "1") (pinfunction "+_1") (pintype "passive"))
      (node (ref "IC1") (pin "1") (pinfunction "GND_1") (pintype "passive"))
      (node (ref "R33") (pin "2") (pinfunction "right_2") (pintype "passive"))
      (node (ref "R37") (pin "2") (pinfunction "right_2") (pintype "passive"))
      (node (ref "R41") (pin "2") (pinfunction "right_2") (pintype "passive"))
      (node (ref "R51") (pin "2") (pinfunction "right_2") (pintype "passive"))
    )
    (net (code "50") (name "Net-(C11-+)") (class "Default")
      (node (ref "C11") (pin "1") (pinfunction "+_1") (pintype "passive"))
      (node (ref "IC6") (pin "10") (pinfunction "MR_10") (pintype "passive"))
      (node (ref "R44") (pin "2") (pinfunction "right_2") (pintype "passive"))
    )
    (net (code "51") (name "Net-(IC2-!Q7)") (class "Default")
      (node (ref "IC2") (pin "9") (pinfunction "!Q7_9") (pintype "passive"))
      (node (ref "IC4") (pin "14") (pinfunction "DATA_14") (pintype "passive"))
    )
    (net (code "52") (name "Net-(IC3-DATA)") (class "Default")
      (node (ref "IC3") (pin "14") (pinfunction "DATA_14") (pintype "passive"))
      (node (ref "IC4") (pin "9") (pinfunction "!Q7_9") (pintype "passive"))
    )
    (net (code "53") (name "Net-(IC5-!Q7)") (class "Default")
      (node (ref "IC5") (pin "9") (pinfunction "!Q7_9") (pintype "passive"))
      (node (ref "IC6") (pin "14") (pinfunction "DATA_14") (pintype "passive"))
    )
    (net (code "54") (name "Net-(LED1-K)") (class "Default")
      (node (ref "LED1") (pin "2") (pinfunction "K_2") (pintype "passive"))
      (node (ref "R1") (pin "2") (pinfunction "right_2") (pintype "passive"))
    )
    (net (code "55") (name "Net-(LED2-K)") (class "Default")
      (node (ref "LED2") (pin "2") (pinfunction "K_2") (pintype "passive"))
      (node (ref "R2") (pin "2") (pinfunction "right_2") (pintype "passive"))
    )
    (net (code "56") (name "Net-(LED3-K)") (class "Default")
      (node (ref "LED3") (pin "2") (pinfunction "K_2") (pintype "passive"))
      (node (ref "R3") (pin "2") (pinfunction "right_2") (pintype "passive"))
    )
    (net (code "57") (name "Net-(LED4-K)") (class "Default")
      (node (ref "LED4") (pin "2") (pinfunction "K_2") (pintype "passive"))
      (node (ref "R4") (pin "2") (pinfunction "right_2") (pintype "passive"))
    )
    (net (code "58") (name "Net-(LED5-K)") (class "Default")
      (node (ref "LED5") (pin "2") (pinfunction "K_2") (pintype "passive"))
      (node (ref "R5") (pin "2") (pinfunction "right_2") (pintype "passive"))
    )
    (net (code "59") (name "Net-(LED6-K)") (class "Default")
      (node (ref "LED6") (pin "2") (pinfunction "K_2") (pintype "passive"))
      (node (ref "R6") (pin "2") (pinfunction "right_2") (pintype "passive"))
    )
    (net (code "60") (name "Net-(LED7-K)") (class "Default")
      (node (ref "LED7") (pin "2") (pinfunction "K_2") (pintype "passive"))
      (node (ref "R7") (pin "2") (pinfunction "right_2") (pintype "passive"))
    )
    (net (code "61") (name "Net-(LED8-K)") (class "Default")
      (node (ref "LED8") (pin "2") (pinfunction "K_2") (pintype "passive"))
      (node (ref "R8") (pin "2") (pinfunction "right_2") (pintype "passive"))
    )
    (net (code "62") (name "Net-(LED9-K)") (class "Default")
      (node (ref "LED9") (pin "2") (pinfunction "K_2") (pintype "passive"))
      (node (ref "R9") (pin "2") (pinfunction "right_2") (pintype "passive"))
    )
    (net (code "63") (name "Net-(LED10-K)") (class "Default")
      (node (ref "LED10") (pin "2") (pinfunction "K_2") (pintype "passive"))
      (node (ref "R10") (pin "2") (pinfunction "right_2") (pintype "passive"))
    )
    (net (code "64") (name "Net-(LED11-K)") (class "Default")
      (node (ref "LED11") (pin "2") (pinfunction "K_2") (pintype "passive"))
      (node (ref "R11") (pin "2") (pinfunction "right_2") (pintype "passive"))
    )
    (net (code "65") (name "Net-(LED12-K)") (class "Default")
      (node (ref "LED12") (pin "2") (pinfunction "K_2") (pintype "passive"))
      (node (ref "R12") (pin "2") (pinfunction "right_2") (pintype "passive"))
    )
    (net (code "66") (name "Net-(LED13-K)") (class "Default")
      (node (ref "LED13") (pin "2") (pinfunction "K_2") (pintype "passive"))
      (node (ref "R13") (pin "2") (pinfunction "right_2") (pintype "passive"))
    )
    (net (code "67") (name "Net-(LED14-K)") (class "Default")
      (node (ref "LED14") (pin "2") (pinfunction "K_2") (pintype "passive"))
      (node (ref "R14") (pin "2") (pinfunction "right_2") (pintype "passive"))
    )
    (net (code "68") (name "Net-(LED15-K)") (class "Default")
      (node (ref "LED15") (pin "2") (pinfunction "K_2") (pintype "passive"))
      (node (ref "R15") (pin "2") (pinfunction "right_2") (pintype "passive"))
    )
    (net (code "69") (name "Net-(LED16-K)") (class "Default")
      (node (ref "LED16") (pin "2") (pinfunction "K_2") (pintype "passive"))
      (node (ref "R16") (pin "2") (pinfunction "right_2") (pintype "passive"))
    )
    (net (code "70") (name "Net-(LED17-K)") (class "Default")
      (node (ref "LED17") (pin "2") (pinfunction "K_2") (pintype "passive"))
      (node (ref "R17") (pin "2") (pinfunction "right_2") (pintype "passive"))
    )
    (net (code "71") (name "Net-(LED18-K)") (class "Default")
      (node (ref "LED18") (pin "2") (pinfunction "K_2") (pintype "passive"))
      (node (ref "R18") (pin "2") (pinfunction "right_2") (pintype "passive"))
    )
    (net (code "72") (name "Net-(LED19-K)") (class "Default")
      (node (ref "LED19") (pin "2") (pinfunction "K_2") (pintype "passive"))
      (node (ref "R19") (pin "2") (pinfunction "right_2") (pintype "passive"))
    )
    (net (code "73") (name "Net-(LED20-K)") (class "Default")
      (node (ref "LED20") (pin "2") (pinfunction "K_2") (pintype "passive"))
      (node (ref "R20") (pin "2") (pinfunction "right_2") (pintype "passive"))
    )
    (net (code "74") (name "Net-(LED21-K)") (class "Default")
      (node (ref "LED21") (pin "2") (pinfunction "K_2") (pintype "passive"))
      (node (ref "R21") (pin "2") (pinfunction "right_2") (pintype "passive"))
    )
    (net (code "75") (name "Net-(LED22-K)") (class "Default")
      (node (ref "LED22") (pin "2") (pinfunction "K_2") (pintype "passive"))
      (node (ref "R22") (pin "2") (pinfunction "right_2") (pintype "passive"))
    )
    (net (code "76") (name "Net-(LED23-K)") (class "Default")
      (node (ref "LED23") (pin "2") (pinfunction "K_2") (pintype "passive"))
      (node (ref "R23") (pin "2") (pinfunction "right_2") (pintype "passive"))
    )
    (net (code "77") (name "Net-(LED24-K)") (class "Default")
      (node (ref "LED24") (pin "2") (pinfunction "K_2") (pintype "passive"))
      (node (ref "R24") (pin "2") (pinfunction "right_2") (pintype "passive"))
    )
    (net (code "78") (name "Net-(LED25-K)") (class "Default")
      (node (ref "LED25") (pin "2") (pinfunction "K_2") (pintype "passive"))
      (node (ref "R25") (pin "2") (pinfunction "right_2") (pintype "passive"))
    )
    (net (code "79") (name "Net-(LED26-K)") (class "Default")
      (node (ref "LED26") (pin "2") (pinfunction "K_2") (pintype "passive"))
      (node (ref "R26") (pin "2") (pinfunction "right_2") (pintype "passive"))
    )
    (net (code "80") (name "Net-(LED27-K)") (class "Default")
      (node (ref "LED27") (pin "2") (pinfunction "K_2") (pintype "passive"))
      (node (ref "R27") (pin "2") (pinfunction "right_2") (pintype "passive"))
    )
    (net (code "81") (name "Net-(LED28-K)") (class "Default")
      (node (ref "LED28") (pin "2") (pinfunction "K_2") (pintype "passive"))
      (node (ref "R28") (pin "2") (pinfunction "right_2") (pintype "passive"))
    )
    (net (code "82") (name "Net-(LED29-K)") (class "Default")
      (node (ref "LED29") (pin "2") (pinfunction "K_2") (pintype "passive"))
      (node (ref "R29") (pin "2") (pinfunction "right_2") (pintype "passive"))
    )
    (net (code "83") (name "Net-(LED30-K)") (class "Default")
      (node (ref "LED30") (pin "2") (pinfunction "K_2") (pintype "passive"))
      (node (ref "R30") (pin "2") (pinfunction "right_2") (pintype "passive"))
    )
    (net (code "84") (name "Net-(LED31-K)") (class "Default")
      (node (ref "LED31") (pin "2") (pinfunction "K_2") (pintype "passive"))
      (node (ref "R31") (pin "2") (pinfunction "right_2") (pintype "passive"))
    )
    (net (code "85") (name "Net-(LED32-K)") (class "Default")
      (node (ref "LED32") (pin "2") (pinfunction "K_2") (pintype "passive"))
      (node (ref "R32") (pin "2") (pinfunction "right_2") (pintype "passive"))
    )
    (net (code "86") (name "Net-(LED33-K)") (class "Default")
      (node (ref "LED33") (pin "2") (pinfunction "K_2") (pintype "passive"))
      (node (ref "R42") (pin "2") (pinfunction "right_2") (pintype "passive"))
    )
    (net (code "87") (name "Net-(LED34-K)") (class "Default")
      (node (ref "LED34") (pin "2") (pinfunction "K_2") (pintype "passive"))
      (node (ref "R50") (pin "2") (pinfunction "right_2") (pintype "passive"))
    )
    (net (code "88") (name "Net-(R34-right)") (class "Default")
      (node (ref "R34") (pin "2") (pinfunction "right_2") (pintype "passive"))
      (node (ref "R37") (pin "1") (pinfunction "left_1") (pintype "passive"))
      (node (ref "R38") (pin "2") (pinfunction "right_2") (pintype "passive"))
    )
    (net (code "89") (name "Net-(R35-right)") (class "Default")
      (node (ref "R35") (pin "2") (pinfunction "right_2") (pintype "passive"))
      (node (ref "R38") (pin "1") (pinfunction "left_1") (pintype "passive"))
      (node (ref "R39") (pin "2") (pinfunction "right_2") (pintype "passive"))
    )
    (net (code "90") (name "Net-(R36-right)") (class "Default")
      (node (ref "R36") (pin "2") (pinfunction "right_2") (pintype "passive"))
      (node (ref "R39") (pin "1") (pinfunction "left_1") (pintype "passive"))
      (node (ref "R40") (pin "2") (pinfunction "right_2") (pintype "passive"))
    )
    (net (code "91") (name "Net-(R43-left)") (class "Default")
      (node (ref "R43") (pin "1") (pinfunction "left_1") (pintype "passive"))
      (node (ref "T1") (pin "1") (pinfunction "1_1") (pintype "passive"))
    )
    (net (code "92") (name "Net-(R45-right)") (class "Default")
      (node (ref "R45") (pin "2") (pinfunction "right_2") (pintype "passive"))
      (node (ref "X1") (pin "2") (pinfunction "2_2") (pintype "passive"))
    )
    (net (code "93") (name "Net-(R46-right)") (class "Default")
      (node (ref "R46") (pin "2") (pinfunction "right_2") (pintype "passive"))
      (node (ref "X1") (pin "3") (pinfunction "3_3") (pintype "passive"))
    )
    (net (code "94") (name "Net-(R47-right)") (class "Default")
      (node (ref "R47") (pin "2") (pinfunction "right_2") (pintype "passive"))
      (node (ref "X1") (pin "4") (pinfunction "4_4") (pintype "passive"))
    )
    (net (code "95") (name "VCC") (class "Default")
      (node (ref "C1") (pin "1") (pinfunction "+_1") (pintype "passive"))
      (node (ref "C2") (pin "1") (pinfunction "+_1") (pintype "passive"))
      (node (ref "C3") (pin "1") (pinfunction "+_1") (pintype "passive"))
      (node (ref "C4") (pin "1") (pinfunction "+_1") (pintype "passive"))
      (node (ref "C5") (pin "1") (pinfunction "+_1") (pintype "passive"))
      (node (ref "C6") (pin "1") (pinfunction "+_1") (pintype "passive"))
      (node (ref "C7") (pin "1") (pinfunction "+_1") (pintype "passive"))
      (node (ref "C8") (pin "1") (pinfunction "+_1") (pintype "passive"))
      (node (ref "IC1") (pin "3") (pinfunction "IN_3") (pintype "passive"))
      (node (ref "IC2") (pin "10") (pinfunction "MR_10") (pintype "passive"))
      (node (ref "IC2") (pin "16") (pinfunction "VCC_16") (pintype "passive"))
      (node (ref "IC3") (pin "10") (pinfunction "MR_10") (pintype "passive"))
      (node (ref "IC3") (pin "16") (pinfunction "VCC_16") (pintype "passive"))
      (node (ref "IC4") (pin "10") (pinfunction "MR_10") (pintype "passive"))
      (node (ref "IC4") (pin "16") (pinfunction "VCC_16") (pintype "passive"))
      (node (ref "IC5") (pin "10") (pinfunction "MR_10") (pintype "passive"))
      (node (ref "IC5") (pin "16") (pinfunction "VCC_16") (pintype "passive"))
      (node (ref "IC6") (pin "16") (pinfunction "VCC_16") (pintype "passive"))
      (node (ref "LED33") (pin "1") (pinfunction "А_1") (pintype "passive"))
      (node (ref "R44") (pin "1") (pinfunction "left_1") (pintype "passive"))
      (node (ref "R48") (pin "1") (pinfunction "left_1") (pintype "passive"))
      (node (ref "R51") (pin "1") (pinfunction "left_1") (pintype "passive"))
      (node (ref "X1") (pin "1") (pinfunction "1_1") (pintype "passive"))
    )
    (net (code "96") (name "unconnected-(H1-Pad1)") (class "Default")
      (node (ref "H1") (pin "1") (pinfunction "1_1") (pintype "passive"))
    )
    (net (code "97") (name "unconnected-(H2-Pad1)") (class "Default")
      (node (ref "H2") (pin "1") (pinfunction "1_1") (pintype "passive"))
    )
    (net (code "98") (name "unconnected-(H3-Pad1)") (class "Default")
      (node (ref "H3") (pin "1") (pinfunction "1_1") (pintype "passive"))
    )
    (net (code "99") (name "unconnected-(H4-Pad1)") (class "Default")
      (node (ref "H4") (pin "1") (pinfunction "1_1") (pintype "passive"))
    )
    (net (code "100") (name "unconnected-(IC6-!Q7-Pad9)") (class "Default")
      (node (ref "IC6") (pin "9") (pinfunction "!Q7_9") (pintype "passive"))
    )
    (net (code "101") (name "unconnected-(IC6-Q4-Pad4)") (class "Default")
      (node (ref "IC6") (pin "4") (pinfunction "Q4_4") (pintype "passive"))
    )
    (net (code "102") (name "unconnected-(IC6-Q5-Pad5)") (class "Default")
      (node (ref "IC6") (pin "5") (pinfunction "Q5_5") (pintype "passive"))
    )
    (net (code "103") (name "unconnected-(IC6-Q6-Pad6)") (class "Default")
      (node (ref "IC6") (pin "6") (pinfunction "Q6_6") (pintype "passive"))
    )
  )
)
